# V0p2_Main_PCB2.net
KiCad netlist of a schematic drawn in EAGLE
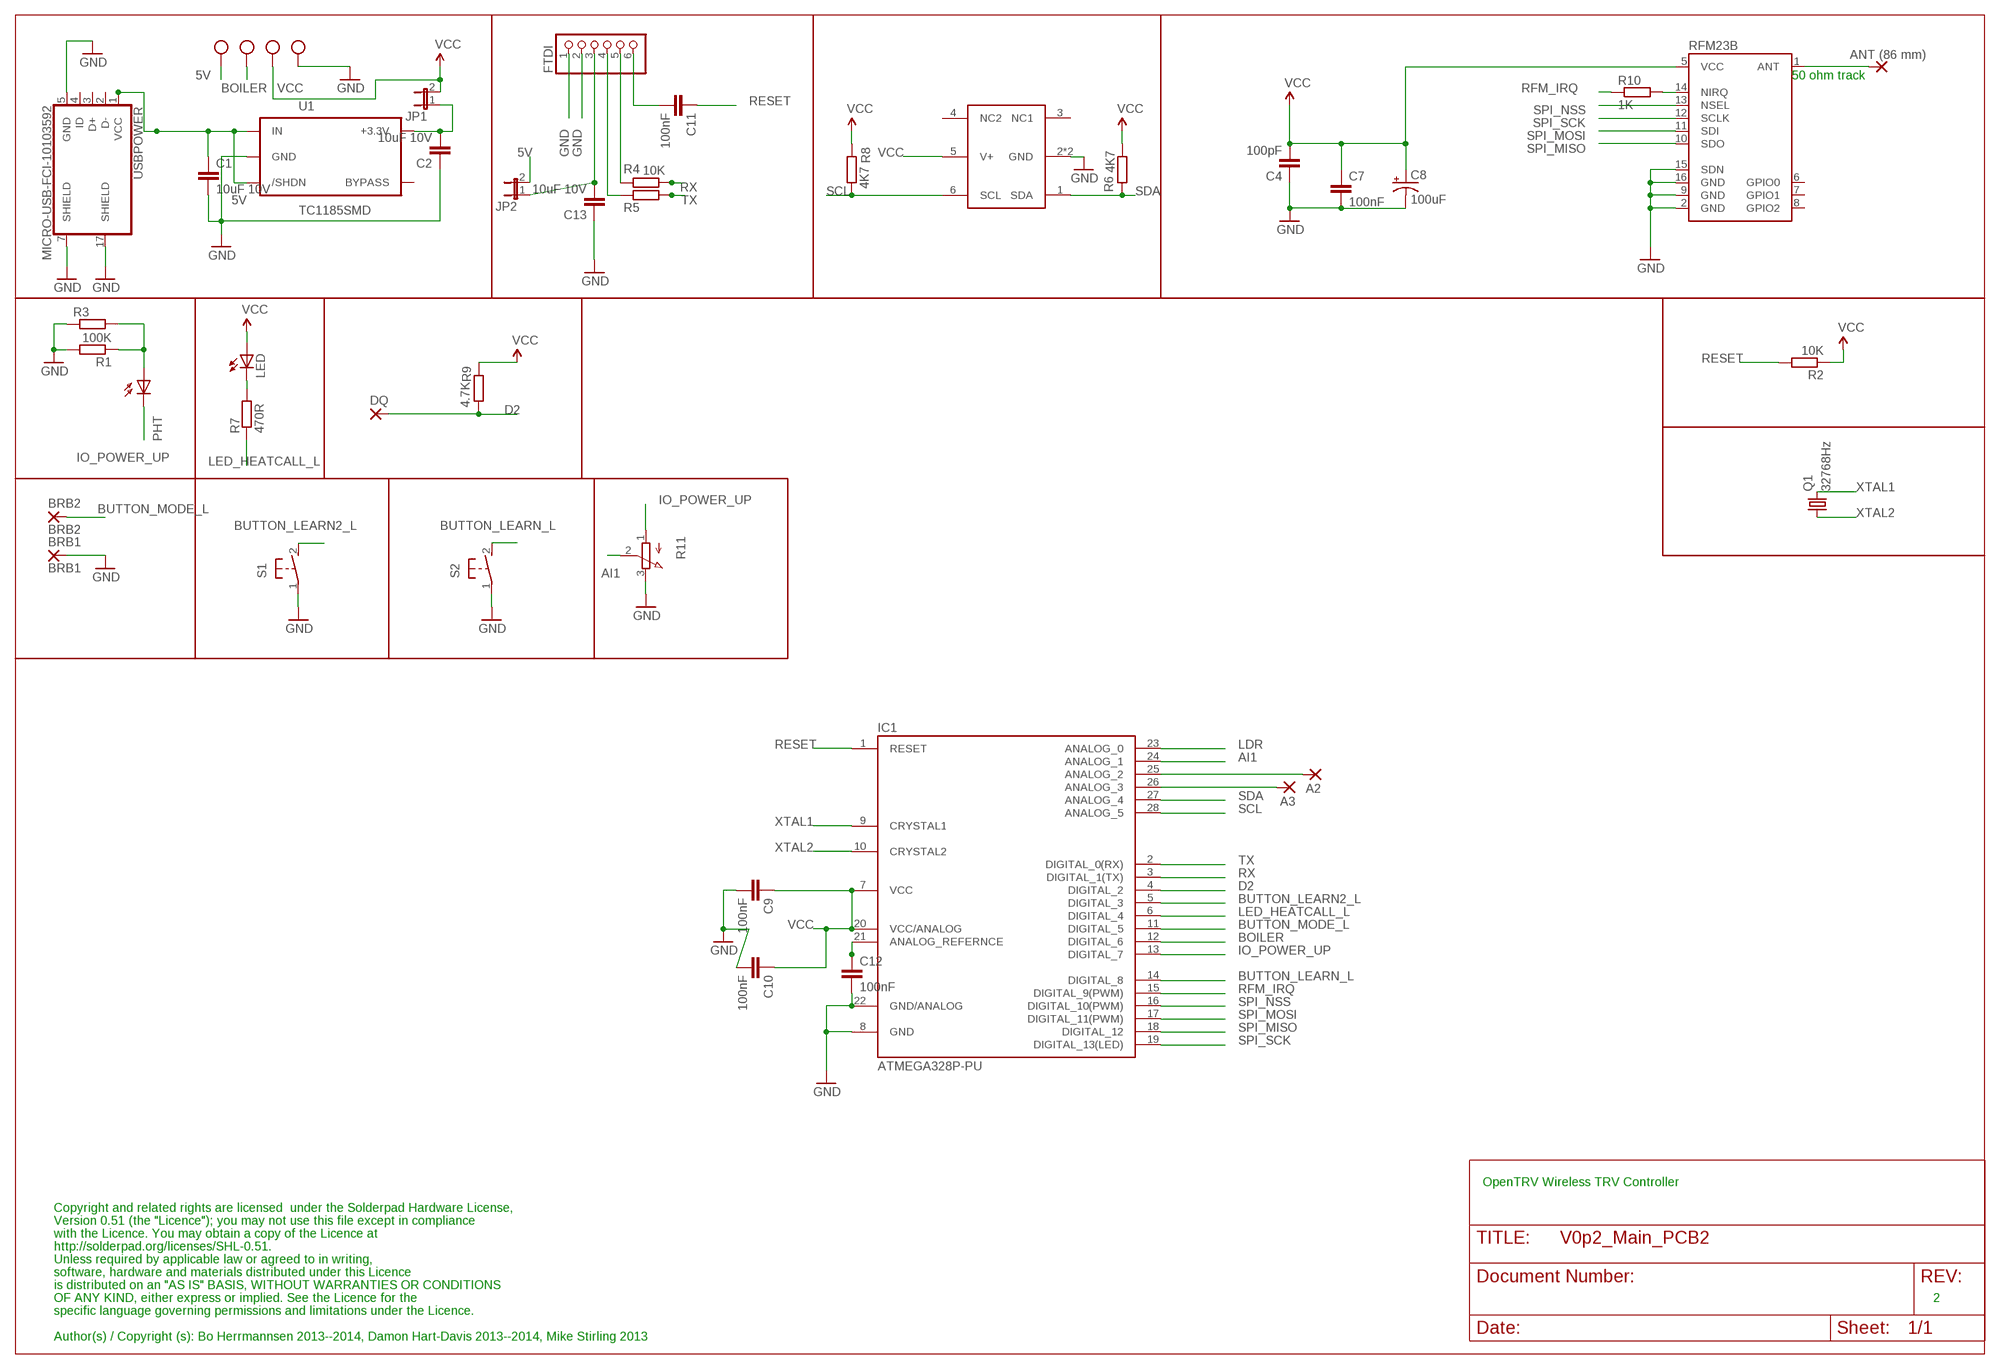
[diagram p0: schematic, sheet 1]

(export (version "E")
  (design (tool "Eeschema 10.0.6"))
  (components
    (comp (ref "A2")
      (value "2,15/1,0")
      (footprint "eagle-import:2,15_1,0")
      (libsource (lib "eagle-import") (part "2,15/1,0"))
    )
    (comp (ref "A3")
      (value "2,15/1,0")
      (footprint "eagle-import:2,15_1,0")
      (libsource (lib "eagle-import") (part "2,15/1,0"))
    )
    (comp (ref "ANT1")
      (value "ANT (86 mm)")
      (footprint "eagle-import:2,15_1,0")
      (libsource (lib "eagle-import") (part "2,15/1,0"))
    )
    (comp (ref "BRB1")
      (value "BRB1")
      (footprint "eagle-import:2,15_1,0")
      (libsource (lib "eagle-import") (part "2,15/1,0"))
    )
    (comp (ref "BRB2")
      (value "BRB2")
      (footprint "eagle-import:2,15_1,0")
      (libsource (lib "eagle-import") (part "2,15/1,0"))
    )
    (comp (ref "C1")
      (value "10uF 10V")
      (footprint "eagle-import:C0603")
      (libsource (lib "eagle-import") (part "C-EUC0603"))
    )
    (comp (ref "C2")
      (value "10uF 10V")
      (footprint "eagle-import:C0603")
      (libsource (lib "eagle-import") (part "C-EUC0603"))
    )
    (comp (ref "C4")
      (value "100pF")
      (footprint "eagle-import:C0603")
      (libsource (lib "eagle-import") (part "C-EUC0603"))
    )
    (comp (ref "C7")
      (value "100nF")
      (footprint "eagle-import:C0603")
      (libsource (lib "eagle-import") (part "C-EUC0603"))
    )
    (comp (ref "C8")
      (value "100uF")
      (footprint "eagle-import:EIA3216")
      (libsource (lib "eagle-import") (part "CAP_POL1206"))
    )
    (comp (ref "C9")
      (value "100nF")
      (footprint "eagle-import:C0603")
      (libsource (lib "eagle-import") (part "C-EUC0603"))
    )
    (comp (ref "C10")
      (value "100nF")
      (footprint "eagle-import:C0603")
      (libsource (lib "eagle-import") (part "C-EUC0603"))
    )
    (comp (ref "C11")
      (value "100nF")
      (footprint "eagle-import:C0603")
      (libsource (lib "eagle-import") (part "C-EUC0603"))
    )
    (comp (ref "C12")
      (value "100nF")
      (footprint "eagle-import:C0603")
      (libsource (lib "eagle-import") (part "C-EUC0603"))
    )
    (comp (ref "C13")
      (value "10uF 10V")
      (footprint "eagle-import:C0603")
      (libsource (lib "eagle-import") (part "C-EUC0603"))
    )
    (comp (ref "DQ")
      (value "2,15/1,0")
      (footprint "eagle-import:2,15_1,0")
      (libsource (lib "eagle-import") (part "2,15/1,0"))
    )
    (comp (ref "FTDI")
      (value "PINHD-1X6/90")
      (footprint "eagle-import:1X06_90")
      (libsource (lib "eagle-import") (part "PINHD-1X6/90"))
    )
    (comp (ref "IC1")
      (value "ATMEGA328P-PU")
      (footprint "eagle-import:DIL28-3")
      (libsource (lib "eagle-import") (part "ATMEGA8-PU"))
    )
    (comp (ref "JP1")
      (value "JP1E")
      (footprint "eagle-import:JP1")
      (libsource (lib "eagle-import") (part "JP1E"))
    )
    (comp (ref "JP2")
      (value "JP1E")
      (footprint "eagle-import:JP1")
      (libsource (lib "eagle-import") (part "JP1E"))
    )
    (comp (ref "LED")
      (value "LED3MM")
      (footprint "eagle-import:LED3MM")
      (libsource (lib "eagle-import") (part "LED3MM"))
    )
    (comp (ref "PHT")
      (value "BPX65")
      (footprint "eagle-import:BPX65")
      (fields (field (name "MPN") "BPX65."))
      (libsource (lib "eagle-import") (part "BPX65"))
    )
    (comp (ref "Q1")
      (value "32768Hz")
      (footprint "eagle-import:MC-306")
      (fields (field (name "MPN") "MC-306 60.0KHZ  100PPM ,12.5PF"))
      (libsource (lib "eagle-import") (part "MC-306"))
    )
    (comp (ref "R1")
      (value "100K")
      (footprint "eagle-import:R0603")
      (libsource (lib "eagle-import") (part "R-EU_R0603"))
    )
    (comp (ref "R2")
      (value "10K")
      (footprint "eagle-import:R0603")
      (libsource (lib "eagle-import") (part "R-EU_R0603"))
    )
    (comp (ref "R3")
      (value "R-EU_0309/V")
      (footprint "eagle-import:0309V")
      (libsource (lib "eagle-import") (part "R-EU_0309/V"))
    )
    (comp (ref "R4")
      (value "10K")
      (footprint "eagle-import:R0603")
      (libsource (lib "eagle-import") (part "R-EU_R0603"))
    )
    (comp (ref "R5")
      (value "10K")
      (footprint "eagle-import:R0603")
      (libsource (lib "eagle-import") (part "R-EU_R0603"))
    )
    (comp (ref "R6")
      (value "4K7")
      (footprint "eagle-import:R0603")
      (libsource (lib "eagle-import") (part "R-EU_R0603"))
    )
    (comp (ref "R7")
      (value "470R")
      (footprint "eagle-import:R0603")
      (libsource (lib "eagle-import") (part "R-EU_R0603"))
    )
    (comp (ref "R8")
      (value "4K7")
      (footprint "eagle-import:R0603")
      (libsource (lib "eagle-import") (part "R-EU_R0603"))
    )
    (comp (ref "R9")
      (value "4.7K")
      (footprint "eagle-import:R0603")
      (libsource (lib "eagle-import") (part "R-EU_R0603"))
    )
    (comp (ref "R10")
      (value "1K")
      (footprint "eagle-import:R0603")
      (libsource (lib "eagle-import") (part "R-EU_R0603"))
    )
    (comp (ref "R11")
      (value "EVUE2A")
      (footprint "eagle-import:EVUE")
      (libsource (lib "eagle-import") (part "EVUE2A"))
    )
    (comp (ref "RFM23B")
      (value "RFM23B")
      (footprint "eagle-import:RFM23-XXX-S1")
      (libsource (lib "eagle-import") (part "RFM23B"))
    )
    (comp (ref "S1")
      (value "31-XX")
      (footprint "eagle-import:B3F-31XX")
      (libsource (lib "eagle-import") (part "31-XX"))
    )
    (comp (ref "S2")
      (value "31-XX")
      (footprint "eagle-import:B3F-31XX")
      (libsource (lib "eagle-import") (part "31-XX"))
    )
    (comp (ref "U$4")
      (value "SHT21")
      (footprint "eagle-import:SHT21")
      (libsource (lib "eagle-import") (part "SHT21"))
    )
    (comp (ref "U1")
      (value "TC1185SMD")
      (footprint "eagle-import:TC1185")
      (libsource (lib "eagle-import") (part "TC1185SMD"))
    )
    (comp (ref "USBPOWER")
      (value "MICRO-USB-FCI-10103592")
      (footprint "eagle-import:MICRO-USB-FCI-10103592")
      (libsource (lib "eagle-import") (part "MICRO-USB-FCI-10103592"))
    )
    (comp (ref "X1")
      (value "W237-102")
      (footprint "eagle-import:SCREWTERMINAL")
      (fields (field (name "MPN") "237-102"))
      (libsource (lib "eagle-import") (part "W237-102"))
    )
    (comp (ref "X2")
      (value "W237-102")
      (footprint "eagle-import:SCREWTERMINAL")
      (fields (field (name "MPN") "237-102"))
      (libsource (lib "eagle-import") (part "W237-102"))
    )
  )
  (nets
    (net (code "1") (name "/5V") (class "Default")
      (node (ref "C1") (pin "1") (pinfunction "1_1") (pintype "passive"))
      (node (ref "JP2") (pin "2") (pinfunction "2_2") (pintype "passive"))
      (node (ref "U1") (pin "1") (pinfunction "IN_1") (pintype "passive"))
      (node (ref "U1") (pin "3") (pinfunction "/SHDN_3") (pintype "passive"))
      (node (ref "USBPOWER") (pin "1") (pinfunction "VCC_1") (pintype "bidirectional"))
      (node (ref "X1") (pin "2") (pinfunction "KL_2") (pintype "passive"))
    )
    (net (code "2") (name "/AI1") (class "Default")
      (node (ref "IC1") (pin "24") (pinfunction "ANALOG_1_24") (pintype "bidirectional"))
      (node (ref "R11") (pin "2") (pinfunction "S_2") (pintype "passive"))
    )
    (net (code "3") (name "/BOILER") (class "Default")
      (node (ref "IC1") (pin "12") (pinfunction "DIGITAL_6_12") (pintype "bidirectional"))
      (node (ref "X1") (pin "1") (pinfunction "KL_1") (pintype "passive"))
    )
    (net (code "4") (name "/BUTTON_LEARN2_L") (class "Default")
      (node (ref "IC1") (pin "5") (pinfunction "DIGITAL_3_5") (pintype "bidirectional"))
      (node (ref "S1") (pin "2") (pinfunction "S_2") (pintype "passive"))
    )
    (net (code "5") (name "/BUTTON_LEARN_L") (class "Default")
      (node (ref "IC1") (pin "14") (pinfunction "DIGITAL_8_14") (pintype "bidirectional"))
      (node (ref "S2") (pin "2") (pinfunction "S_2") (pintype "passive"))
    )
    (net (code "6") (name "/BUTTON_MODE_L") (class "Default")
      (node (ref "BRB2") (pin "1") (pinfunction "P_1") (pintype "passive"))
      (node (ref "IC1") (pin "11") (pinfunction "DIGITAL_5_11") (pintype "bidirectional"))
    )
    (net (code "7") (name "/D2") (class "Default")
      (node (ref "DQ") (pin "1") (pinfunction "P_1") (pintype "passive"))
      (node (ref "IC1") (pin "4") (pinfunction "DIGITAL_2_4") (pintype "bidirectional"))
      (node (ref "R9") (pin "1") (pinfunction "1_1") (pintype "passive"))
    )
    (net (code "8") (name "/IO_POWER_UP") (class "Default")
      (node (ref "IC1") (pin "13") (pinfunction "DIGITAL_7_13") (pintype "bidirectional"))
      (node (ref "PHT") (pin "K") (pinfunction "C_K") (pintype "passive"))
      (node (ref "R11") (pin "1") (pinfunction "A_1") (pintype "passive"))
    )
    (net (code "9") (name "/LDR") (class "Default")
      (node (ref "IC1") (pin "23") (pinfunction "ANALOG_0_23") (pintype "bidirectional"))
      (node (ref "PHT") (pin "A") (pinfunction "A_A") (pintype "passive"))
      (node (ref "R1") (pin "1") (pinfunction "1_1") (pintype "passive"))
      (node (ref "R3") (pin "2") (pinfunction "2_2") (pintype "passive"))
    )
    (net (code "10") (name "/LED_HEATCALL_L") (class "Default")
      (node (ref "IC1") (pin "6") (pinfunction "DIGITAL_4_6") (pintype "bidirectional"))
      (node (ref "R7") (pin "1") (pinfunction "1_1") (pintype "passive"))
    )
    (net (code "11") (name "/RESET") (class "Default")
      (node (ref "C11") (pin "1") (pinfunction "1_1") (pintype "passive"))
      (node (ref "IC1") (pin "1") (pinfunction "RESET_1") (pintype "bidirectional"))
      (node (ref "R2") (pin "2") (pinfunction "2_2") (pintype "passive"))
    )
    (net (code "12") (name "/RFM_IRQ") (class "Default")
      (node (ref "IC1") (pin "15") (pinfunction "DIGITAL_9(PWM)_15") (pintype "bidirectional"))
      (node (ref "R10") (pin "1") (pinfunction "1_1") (pintype "passive"))
    )
    (net (code "13") (name "/RX") (class "Default")
      (node (ref "IC1") (pin "3") (pinfunction "DIGITAL_1(TX)_3") (pintype "bidirectional"))
      (node (ref "R4") (pin "1") (pinfunction "1_1") (pintype "passive"))
    )
    (net (code "14") (name "/SCL") (class "Default")
      (node (ref "IC1") (pin "28") (pinfunction "ANALOG_5_28") (pintype "bidirectional"))
      (node (ref "R8") (pin "1") (pinfunction "1_1") (pintype "passive"))
      (node (ref "U$4") (pin "6") (pinfunction "SCL_6") (pintype "bidirectional"))
    )
    (net (code "15") (name "/SDA") (class "Default")
      (node (ref "IC1") (pin "27") (pinfunction "ANALOG_4_27") (pintype "bidirectional"))
      (node (ref "R6") (pin "2") (pinfunction "2_2") (pintype "passive"))
      (node (ref "U$4") (pin "1") (pinfunction "SDA_1") (pintype "bidirectional"))
    )
    (net (code "16") (name "/SPI_MISO") (class "Default")
      (node (ref "IC1") (pin "18") (pinfunction "DIGITAL_12_18") (pintype "bidirectional"))
      (node (ref "RFM23B") (pin "10") (pinfunction "SDO_10") (pintype "output"))
    )
    (net (code "17") (name "/SPI_MOSI") (class "Default")
      (node (ref "IC1") (pin "17") (pinfunction "DIGITAL_11(PWM)_17") (pintype "bidirectional"))
      (node (ref "RFM23B") (pin "11") (pinfunction "SDI_11") (pintype "input"))
    )
    (net (code "18") (name "/SPI_NSS") (class "Default")
      (node (ref "IC1") (pin "16") (pinfunction "DIGITAL_10(PWM)_16") (pintype "bidirectional"))
      (node (ref "RFM23B") (pin "13") (pinfunction "NSEL_13") (pintype "input"))
    )
    (net (code "19") (name "/SPI_SCK") (class "Default")
      (node (ref "IC1") (pin "19") (pinfunction "DIGITAL_13(LED)_19") (pintype "bidirectional"))
      (node (ref "RFM23B") (pin "12") (pinfunction "SCLK_12") (pintype "input"))
    )
    (net (code "20") (name "/TX") (class "Default")
      (node (ref "IC1") (pin "2") (pinfunction "DIGITAL_0(RX)_2") (pintype "bidirectional"))
      (node (ref "R5") (pin "1") (pinfunction "1_1") (pintype "passive"))
    )
    (net (code "21") (name "/XTAL1") (class "Default")
      (node (ref "IC1") (pin "9") (pinfunction "CRYSTAL1_9") (pintype "bidirectional"))
      (node (ref "Q1") (pin "4") (pinfunction "2_4") (pintype "passive"))
    )
    (net (code "22") (name "/XTAL2") (class "Default")
      (node (ref "IC1") (pin "10") (pinfunction "CRYSTAL2_10") (pintype "bidirectional"))
      (node (ref "Q1") (pin "1") (pinfunction "1_1") (pintype "passive"))
    )
    (net (code "23") (name "GND") (class "Default")
      (node (ref "BRB1") (pin "1") (pinfunction "P_1") (pintype "passive"))
      (node (ref "C1") (pin "2") (pinfunction "2_2") (pintype "passive"))
      (node (ref "C10") (pin "2") (pinfunction "2_2") (pintype "passive"))
      (node (ref "C12") (pin "2") (pinfunction "2_2") (pintype "passive"))
      (node (ref "C13") (pin "1") (pinfunction "1_1") (pintype "passive"))
      (node (ref "C2") (pin "1") (pinfunction "1_1") (pintype "passive"))
      (node (ref "C4") (pin "1") (pinfunction "1_1") (pintype "passive"))
      (node (ref "C7") (pin "2") (pinfunction "2_2") (pintype "passive"))
      (node (ref "C8") (pin "C") (pinfunction "-_C") (pintype "passive"))
      (node (ref "C9") (pin "2") (pinfunction "2_2") (pintype "passive"))
      (node (ref "FTDI") (pin "1") (pinfunction "1_1") (pintype "passive"))
      (node (ref "FTDI") (pin "2") (pinfunction "2_2") (pintype "passive"))
      (node (ref "IC1") (pin "22") (pinfunction "GND/ANALOG_22") (pintype "power_in"))
      (node (ref "IC1") (pin "8") (pinfunction "GND_8") (pintype "power_in"))
      (node (ref "R1") (pin "2") (pinfunction "2_2") (pintype "passive"))
      (node (ref "R11") (pin "3") (pinfunction "E_3") (pintype "passive"))
      (node (ref "R3") (pin "1") (pinfunction "1_1") (pintype "passive"))
      (node (ref "RFM23B") (pin "15") (pinfunction "SDN_15") (pintype "input"))
      (node (ref "RFM23B") (pin "16") (pinfunction "GND_16") (pintype "power_in"))
      (node (ref "RFM23B") (pin "2") (pinfunction "GND_2") (pintype "power_in"))
      (node (ref "RFM23B") (pin "9") (pinfunction "GND_9") (pintype "power_in"))
      (node (ref "S1") (pin "1") (pinfunction "P_1") (pintype "passive"))
      (node (ref "S2") (pin "1") (pinfunction "P_1") (pintype "passive"))
      (node (ref "U$4") (pin "2") (pinfunction "GND_2") (pintype "bidirectional"))
      (node (ref "U$4") (pin "P$1") (pinfunction "GND_P$1") (pintype "bidirectional"))
      (node (ref "U1") (pin "2") (pinfunction "GND_2") (pintype "passive"))
      (node (ref "USBPOWER") (pin "17") (pinfunction "SHIELD_17") (pintype "bidirectional"))
      (node (ref "USBPOWER") (pin "5") (pinfunction "GND_5") (pintype "bidirectional"))
      (node (ref "USBPOWER") (pin "7") (pinfunction "SHIELD_7") (pintype "bidirectional"))
      (node (ref "X2") (pin "2") (pinfunction "KL_2") (pintype "passive"))
    )
    (net (code "24") (name "Net-(A2-P)") (class "Default")
      (node (ref "A2") (pin "1") (pinfunction "P_1") (pintype "passive"))
      (node (ref "IC1") (pin "25") (pinfunction "ANALOG_2_25") (pintype "bidirectional"))
    )
    (net (code "25") (name "Net-(A3-P)") (class "Default")
      (node (ref "A3") (pin "1") (pinfunction "P_1") (pintype "passive"))
      (node (ref "IC1") (pin "26") (pinfunction "ANALOG_3_26") (pintype "bidirectional"))
    )
    (net (code "26") (name "Net-(ANT1-P)") (class "Default")
      (node (ref "ANT1") (pin "1") (pinfunction "P_1") (pintype "passive"))
      (node (ref "RFM23B") (pin "1") (pinfunction "ANT_1") (pintype "bidirectional"))
    )
    (net (code "27") (name "Net-(C11-Pad2)") (class "Default")
      (node (ref "C11") (pin "2") (pinfunction "2_2") (pintype "passive"))
      (node (ref "FTDI") (pin "6") (pinfunction "6_6") (pintype "passive"))
    )
    (net (code "28") (name "Net-(C13-Pad2)") (class "Default")
      (node (ref "C13") (pin "2") (pinfunction "2_2") (pintype "passive"))
      (node (ref "FTDI") (pin "3") (pinfunction "3_3") (pintype "passive"))
      (node (ref "JP2") (pin "1") (pinfunction "1_1") (pintype "passive"))
    )
    (net (code "29") (name "Net-(FTDI-Pad4)") (class "Default")
      (node (ref "FTDI") (pin "4") (pinfunction "4_4") (pintype "passive"))
      (node (ref "R5") (pin "2") (pinfunction "2_2") (pintype "passive"))
    )
    (net (code "30") (name "Net-(FTDI-Pad5)") (class "Default")
      (node (ref "FTDI") (pin "5") (pinfunction "5_5") (pintype "passive"))
      (node (ref "R4") (pin "2") (pinfunction "2_2") (pintype "passive"))
    )
    (net (code "31") (name "Net-(IC1-ANALOG_REFERNCE)") (class "Default")
      (node (ref "C12") (pin "1") (pinfunction "1_1") (pintype "passive"))
      (node (ref "IC1") (pin "21") (pinfunction "ANALOG_REFERNCE_21") (pintype "passive"))
    )
    (net (code "32") (name "Net-(LED-C)") (class "Default")
      (node (ref "LED") (pin "K") (pinfunction "C_K") (pintype "passive"))
      (node (ref "R7") (pin "2") (pinfunction "2_2") (pintype "passive"))
    )
    (net (code "33") (name "Net-(RFM23B-NIRQ)") (class "Default")
      (node (ref "R10") (pin "2") (pinfunction "2_2") (pintype "passive"))
      (node (ref "RFM23B") (pin "14") (pinfunction "NIRQ_14") (pintype "output"))
    )
    (net (code "34") (name "Net-(U1-+3.3V)") (class "Default")
      (node (ref "C2") (pin "2") (pinfunction "2_2") (pintype "passive"))
      (node (ref "JP1") (pin "1") (pinfunction "1_1") (pintype "passive"))
      (node (ref "U1") (pin "5") (pinfunction "+3.3V_5") (pintype "power_in"))
    )
    (net (code "35") (name "VCC") (class "Default")
      (node (ref "C10") (pin "1") (pinfunction "1_1") (pintype "passive"))
      (node (ref "C4") (pin "2") (pinfunction "2_2") (pintype "passive"))
      (node (ref "C7") (pin "1") (pinfunction "1_1") (pintype "passive"))
      (node (ref "C8") (pin "A") (pinfunction "+_A") (pintype "passive"))
      (node (ref "C9") (pin "1") (pinfunction "1_1") (pintype "passive"))
      (node (ref "IC1") (pin "20") (pinfunction "VCC/ANALOG_20") (pintype "passive"))
      (node (ref "IC1") (pin "7") (pinfunction "VCC_7") (pintype "power_in"))
      (node (ref "JP1") (pin "2") (pinfunction "2_2") (pintype "passive"))
      (node (ref "LED") (pin "A") (pinfunction "A_A") (pintype "passive"))
      (node (ref "R2") (pin "1") (pinfunction "1_1") (pintype "passive"))
      (node (ref "R6") (pin "1") (pinfunction "1_1") (pintype "passive"))
      (node (ref "R8") (pin "2") (pinfunction "2_2") (pintype "passive"))
      (node (ref "R9") (pin "2") (pinfunction "2_2") (pintype "passive"))
      (node (ref "RFM23B") (pin "5") (pinfunction "VCC_5") (pintype "bidirectional"))
      (node (ref "U$4") (pin "5") (pinfunction "V+_5") (pintype "bidirectional"))
      (node (ref "X2") (pin "1") (pinfunction "KL_1") (pintype "passive"))
    )
    (net (code "36") (name "unconnected-(RFM23B-GPIO0-Pad6)") (class "Default")
      (node (ref "RFM23B") (pin "6") (pinfunction "GPIO0_6") (pintype "bidirectional"))
    )
    (net (code "37") (name "unconnected-(RFM23B-GPIO1-Pad7)") (class "Default")
      (node (ref "RFM23B") (pin "7") (pinfunction "GPIO1_7") (pintype "bidirectional"))
    )
    (net (code "38") (name "unconnected-(RFM23B-GPIO2-Pad8)") (class "Default")
      (node (ref "RFM23B") (pin "8") (pinfunction "GPIO2_8") (pintype "bidirectional"))
    )
    (net (code "39") (name "unconnected-(U$4-NC1-Pad3)") (class "Default")
      (node (ref "U$4") (pin "3") (pinfunction "NC1_3") (pintype "bidirectional"))
    )
    (net (code "40") (name "unconnected-(U$4-NC2-Pad4)") (class "Default")
      (node (ref "U$4") (pin "4") (pinfunction "NC2_4") (pintype "bidirectional"))
    )
    (net (code "41") (name "unconnected-(U1-BYPASS-Pad4)") (class "Default")
      (node (ref "U1") (pin "4") (pinfunction "BYPASS_4") (pintype "passive"))
    )
    (net (code "42") (name "unconnected-(USBPOWER-D+-Pad3)") (class "Default")
      (node (ref "USBPOWER") (pin "3") (pinfunction "D+_3") (pintype "bidirectional"))
    )
    (net (code "43") (name "unconnected-(USBPOWER-D--Pad2)") (class "Default")
      (node (ref "USBPOWER") (pin "2") (pinfunction "D-_2") (pintype "bidirectional"))
    )
    (net (code "44") (name "unconnected-(USBPOWER-ID-Pad4)") (class "Default")
      (node (ref "USBPOWER") (pin "4") (pinfunction "ID_4") (pintype "bidirectional"))
    )
  )
)
